# Raspberry_pi_hat.net
KiCad netlist of a schematic drawn in Altium Designer
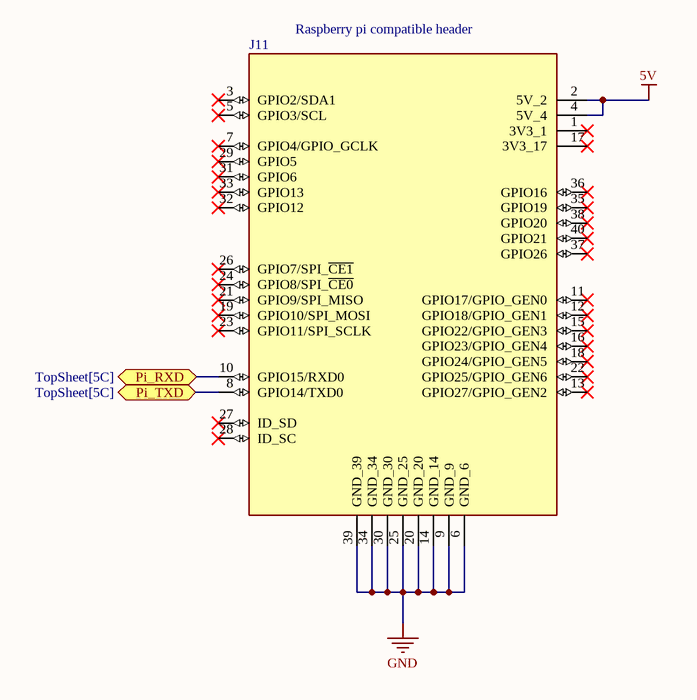
[diagram p0: Raspberry_pi_hat.SchDoc]

(export (version "E")
  (design (tool "Eeschema 10.0.6"))
  (components
    (comp (ref "J11")
      (value "Raspberry pi compatible header")
      (footprint "pi_header")
      (libsource (lib "pi_header") (part "pi_header"))
    )
  )
  (nets
    (net (code "1") (name "/Pi_RXD") (class "Default")
      (node (ref "J11") (pin "10") (pinfunction "GPIO15/RXD0_10") (pintype "bidirectional"))
    )
    (net (code "2") (name "/Pi_TXD") (class "Default")
      (node (ref "J11") (pin "8") (pinfunction "GPIO14/TXD0_8") (pintype "bidirectional"))
    )
    (net (code "3") (name "5V") (class "Default")
      (node (ref "J11") (pin "2") (pinfunction "5V_2_2") (pintype "power_in"))
      (node (ref "J11") (pin "4") (pinfunction "5V_4_4") (pintype "power_in"))
    )
    (net (code "4") (name "GND") (class "Default")
      (node (ref "J11") (pin "14") (pinfunction "GND_14_14") (pintype "power_in"))
      (node (ref "J11") (pin "20") (pinfunction "GND_20_20") (pintype "power_in"))
      (node (ref "J11") (pin "25") (pinfunction "GND_25_25") (pintype "power_in"))
      (node (ref "J11") (pin "30") (pinfunction "GND_30_30") (pintype "power_in"))
      (node (ref "J11") (pin "34") (pinfunction "GND_34_34") (pintype "power_in"))
      (node (ref "J11") (pin "39") (pinfunction "GND_39_39") (pintype "power_in"))
      (node (ref "J11") (pin "6") (pinfunction "GND_6_6") (pintype "power_in"))
      (node (ref "J11") (pin "9") (pinfunction "GND_9_9") (pintype "power_in"))
    )
    (net (code "5") (name "unconnected-(J11-3V3_1-Pad1)") (class "Default")
      (node (ref "J11") (pin "1") (pinfunction "3V3_1_1") (pintype "power_in+no_connect"))
    )
    (net (code "6") (name "unconnected-(J11-3V3_17-Pad17)") (class "Default")
      (node (ref "J11") (pin "17") (pinfunction "3V3_17_17") (pintype "power_in+no_connect"))
    )
    (net (code "7") (name "unconnected-(J11-GPIO2{slash}SDA1-Pad3)") (class "Default")
      (node (ref "J11") (pin "3") (pinfunction "GPIO2/SDA1_3") (pintype "bidirectional+no_connect"))
    )
    (net (code "8") (name "unconnected-(J11-GPIO3{slash}SCL-Pad5)") (class "Default")
      (node (ref "J11") (pin "5") (pinfunction "GPIO3/SCL_5") (pintype "bidirectional+no_connect"))
    )
    (net (code "9") (name "unconnected-(J11-GPIO4{slash}GPIO_GCLK-Pad7)") (class "Default")
      (node (ref "J11") (pin "7") (pinfunction "GPIO4/GPIO_GCLK_7") (pintype "bidirectional+no_connect"))
    )
    (net (code "10") (name "unconnected-(J11-GPIO5-Pad29)") (class "Default")
      (node (ref "J11") (pin "29") (pinfunction "GPIO5_29") (pintype "bidirectional+no_connect"))
    )
    (net (code "11") (name "unconnected-(J11-GPIO6-Pad31)") (class "Default")
      (node (ref "J11") (pin "31") (pinfunction "GPIO6_31") (pintype "bidirectional+no_connect"))
    )
    (net (code "12") (name "unconnected-(J11-GPIO7{slash}SPI_~{CE1}-Pad26)") (class "Default")
      (node (ref "J11") (pin "26") (pinfunction "GPIO7/SPI_~{CE1}_26") (pintype "bidirectional+no_connect"))
    )
    (net (code "13") (name "unconnected-(J11-GPIO8{slash}SPI_~{CE0}-Pad24)") (class "Default")
      (node (ref "J11") (pin "24") (pinfunction "GPIO8/SPI_~{CE0}_24") (pintype "bidirectional+no_connect"))
    )
    (net (code "14") (name "unconnected-(J11-GPIO9{slash}SPI_MISO-Pad21)") (class "Default")
      (node (ref "J11") (pin "21") (pinfunction "GPIO9/SPI_MISO_21") (pintype "bidirectional+no_connect"))
    )
    (net (code "15") (name "unconnected-(J11-GPIO10{slash}SPI_MOSI-Pad19)") (class "Default")
      (node (ref "J11") (pin "19") (pinfunction "GPIO10/SPI_MOSI_19") (pintype "bidirectional+no_connect"))
    )
    (net (code "16") (name "unconnected-(J11-GPIO11{slash}SPI_SCLK-Pad23)") (class "Default")
      (node (ref "J11") (pin "23") (pinfunction "GPIO11/SPI_SCLK_23") (pintype "bidirectional+no_connect"))
    )
    (net (code "17") (name "unconnected-(J11-GPIO12-Pad32)") (class "Default")
      (node (ref "J11") (pin "32") (pinfunction "GPIO12_32") (pintype "bidirectional+no_connect"))
    )
    (net (code "18") (name "unconnected-(J11-GPIO13-Pad33)") (class "Default")
      (node (ref "J11") (pin "33") (pinfunction "GPIO13_33") (pintype "bidirectional+no_connect"))
    )
    (net (code "19") (name "unconnected-(J11-GPIO16-Pad36)") (class "Default")
      (node (ref "J11") (pin "36") (pinfunction "GPIO16_36") (pintype "bidirectional+no_connect"))
    )
    (net (code "20") (name "unconnected-(J11-GPIO17{slash}GPIO_GEN0-Pad11)") (class "Default")
      (node (ref "J11") (pin "11") (pinfunction "GPIO17/GPIO_GEN0_11") (pintype "bidirectional+no_connect"))
    )
    (net (code "21") (name "unconnected-(J11-GPIO18{slash}GPIO_GEN1-Pad12)") (class "Default")
      (node (ref "J11") (pin "12") (pinfunction "GPIO18/GPIO_GEN1_12") (pintype "bidirectional+no_connect"))
    )
    (net (code "22") (name "unconnected-(J11-GPIO19-Pad35)") (class "Default")
      (node (ref "J11") (pin "35") (pinfunction "GPIO19_35") (pintype "bidirectional+no_connect"))
    )
    (net (code "23") (name "unconnected-(J11-GPIO20-Pad38)") (class "Default")
      (node (ref "J11") (pin "38") (pinfunction "GPIO20_38") (pintype "bidirectional+no_connect"))
    )
    (net (code "24") (name "unconnected-(J11-GPIO21-Pad40)") (class "Default")
      (node (ref "J11") (pin "40") (pinfunction "GPIO21_40") (pintype "bidirectional+no_connect"))
    )
    (net (code "25") (name "unconnected-(J11-GPIO22{slash}GPIO_GEN3-Pad15)") (class "Default")
      (node (ref "J11") (pin "15") (pinfunction "GPIO22/GPIO_GEN3_15") (pintype "bidirectional+no_connect"))
    )
    (net (code "26") (name "unconnected-(J11-GPIO23{slash}GPIO_GEN4-Pad16)") (class "Default")
      (node (ref "J11") (pin "16") (pinfunction "GPIO23/GPIO_GEN4_16") (pintype "bidirectional+no_connect"))
    )
    (net (code "27") (name "unconnected-(J11-GPIO24{slash}GPIO_GEN5-Pad18)") (class "Default")
      (node (ref "J11") (pin "18") (pinfunction "GPIO24/GPIO_GEN5_18") (pintype "bidirectional+no_connect"))
    )
    (net (code "28") (name "unconnected-(J11-GPIO25{slash}GPIO_GEN6-Pad22)") (class "Default")
      (node (ref "J11") (pin "22") (pinfunction "GPIO25/GPIO_GEN6_22") (pintype "bidirectional+no_connect"))
    )
    (net (code "29") (name "unconnected-(J11-GPIO26-Pad37)") (class "Default")
      (node (ref "J11") (pin "37") (pinfunction "GPIO26_37") (pintype "bidirectional+no_connect"))
    )
    (net (code "30") (name "unconnected-(J11-GPIO27{slash}GPIO_GEN2-Pad13)") (class "Default")
      (node (ref "J11") (pin "13") (pinfunction "GPIO27/GPIO_GEN2_13") (pintype "bidirectional+no_connect"))
    )
    (net (code "31") (name "unconnected-(J11-ID_SC-Pad28)") (class "Default")
      (node (ref "J11") (pin "28") (pinfunction "ID_SC_28") (pintype "bidirectional+no_connect"))
    )
    (net (code "32") (name "unconnected-(J11-ID_SD-Pad27)") (class "Default")
      (node (ref "J11") (pin "27") (pinfunction "ID_SD_27") (pintype "bidirectional+no_connect"))
    )
  )
)
